# Schematic.net
KiCad netlist of a schematic drawn in EAGLE
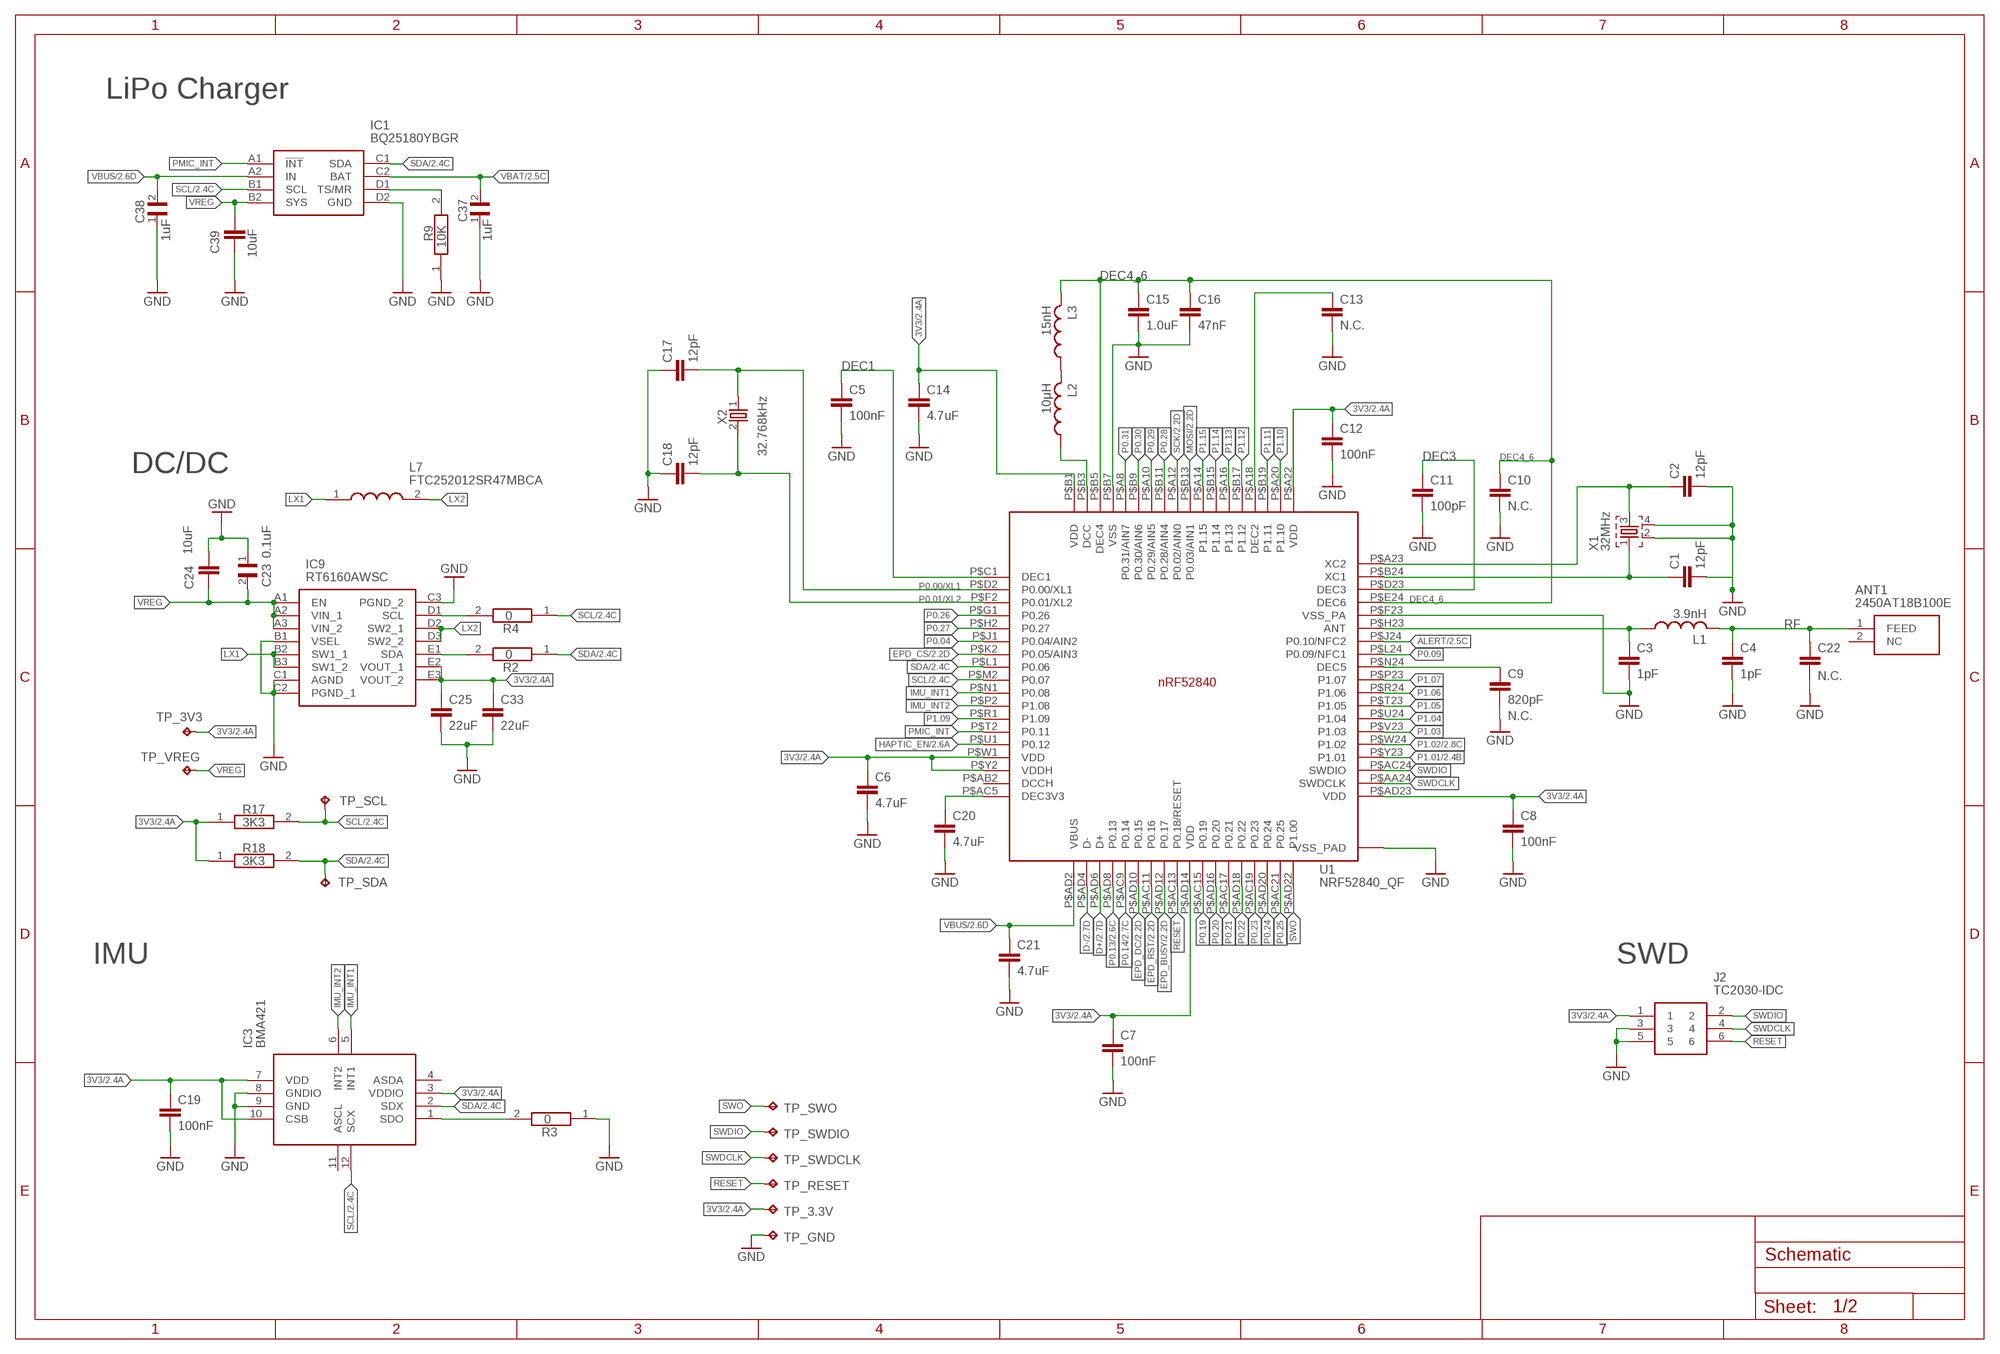
[diagram p0: schematic, sheet 1]
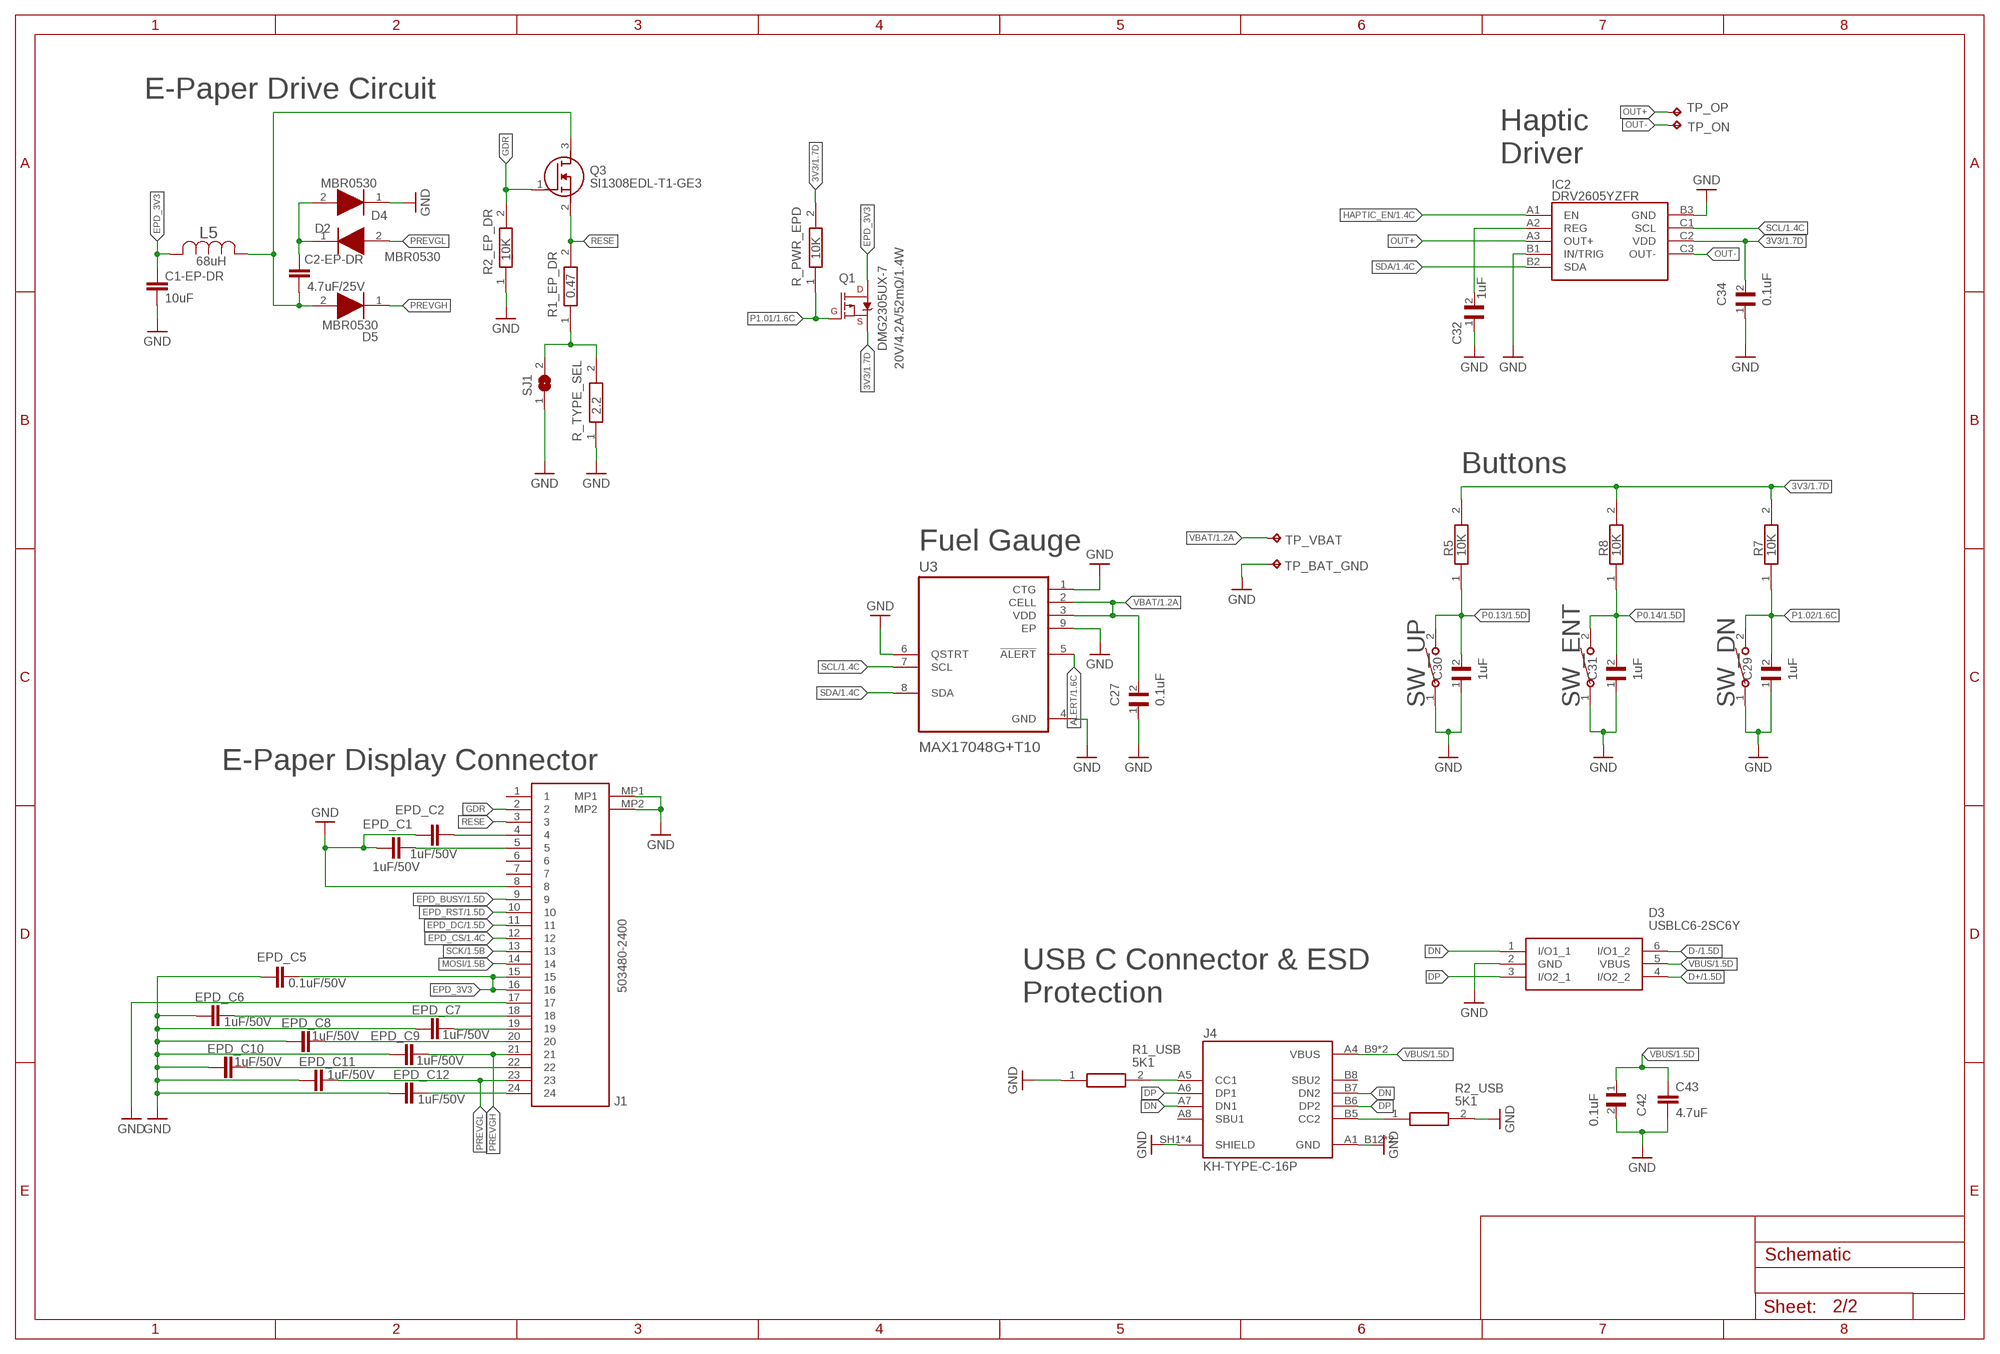
[diagram p1: schematic, sheet 2]

(export (version "E")
  (design (tool "Eeschema 10.0.6"))
  (components
    (comp (ref "ANT1")
      (value "2450AT18B100E")
      (footprint "eagle-import:2450AT18B100E_ANTC3216X140N")
      (fields (field (name "MOUSER_PART_NUMBER") "609-2450AT18B100E"))
      (libsource (lib "eagle-import") (part "2450AT18B100E_2450AT18B100E"))
    )
    (comp (ref "C1")
      (value "12pF")
      (footprint "eagle-import:NORDIC_NRF_3_RESC0201_L")
      (libsource (lib "eagle-import") (part "NORDIC_NRF_3_CAPACITOR_0201_L"))
    )
    (comp (ref "C2")
      (value "12pF")
      (footprint "eagle-import:NORDIC_NRF_3_RESC0201_L")
      (libsource (lib "eagle-import") (part "NORDIC_NRF_3_CAPACITOR_0201_L"))
    )
    (comp (ref "C3")
      (value "1pF")
      (footprint "eagle-import:NORDIC_NRF_3_RESC0201_L")
      (libsource (lib "eagle-import") (part "NORDIC_NRF_3_CAPACITOR_0201_L"))
    )
    (comp (ref "C4")
      (value "1pF")
      (footprint "eagle-import:NORDIC_NRF_3_RESC0201_L")
      (libsource (lib "eagle-import") (part "NORDIC_NRF_3_CAPACITOR_0201_L"))
    )
    (comp (ref "C5")
      (value "100nF")
      (footprint "eagle-import:NORDIC_NRF_3_RESC0201_L")
      (libsource (lib "eagle-import") (part "NORDIC_NRF_3_CAPACITOR_0201_L"))
    )
    (comp (ref "C6")
      (value "4.7uF")
      (footprint "eagle-import:NORDIC_NRF_3_RESC0402_L")
      (libsource (lib "eagle-import") (part "NORDIC_NRF_3_CAPACITOR_0402_L"))
    )
    (comp (ref "C7")
      (value "100nF")
      (footprint "eagle-import:NORDIC_NRF_3_RESC0201_L")
      (libsource (lib "eagle-import") (part "NORDIC_NRF_3_CAPACITOR_0201_L"))
    )
    (comp (ref "C8")
      (value "100nF")
      (footprint "eagle-import:NORDIC_NRF_3_RESC0201_L")
      (libsource (lib "eagle-import") (part "NORDIC_NRF_3_CAPACITOR_0201_L"))
    )
    (comp (ref "C9")
      (value "820pF")
      (footprint "eagle-import:NORDIC_NRF_3_RESC0201_L")
      (libsource (lib "eagle-import") (part "NORDIC_NRF_3_CAPACITOR_0201_L"))
    )
    (comp (ref "C10")
      (value "N.C.")
      (footprint "eagle-import:NORDIC_NRF_3_RESC0201_L")
      (libsource (lib "eagle-import") (part "NORDIC_NRF_3_CAPACITOR_0201_L"))
    )
    (comp (ref "C11")
      (value "100pF")
      (footprint "eagle-import:NORDIC_NRF_3_RESC0201_L")
      (libsource (lib "eagle-import") (part "NORDIC_NRF_3_CAPACITOR_0201_L"))
    )
    (comp (ref "C12")
      (value "100nF")
      (footprint "eagle-import:NORDIC_NRF_3_RESC0201_L")
      (libsource (lib "eagle-import") (part "NORDIC_NRF_3_CAPACITOR_0201_L"))
    )
    (comp (ref "C13")
      (value "N.C.")
      (footprint "eagle-import:NORDIC_NRF_3_RESC0201_L")
      (libsource (lib "eagle-import") (part "NORDIC_NRF_3_CAPACITOR_0201_L"))
    )
    (comp (ref "C14")
      (value "4.7uF")
      (footprint "eagle-import:NORDIC_NRF_3_RESC0402_L")
      (libsource (lib "eagle-import") (part "NORDIC_NRF_3_CAPACITOR_0402_L"))
    )
    (comp (ref "C15")
      (value "1.0uF")
      (footprint "eagle-import:NORDIC_NRF_3_RESC0402_L")
      (libsource (lib "eagle-import") (part "NORDIC_NRF_3_CAPACITOR_0402_L"))
    )
    (comp (ref "C16")
      (value "47nF")
      (footprint "eagle-import:NORDIC_NRF_3_RESC0201_L")
      (libsource (lib "eagle-import") (part "NORDIC_NRF_3_CAPACITOR_0201_L"))
    )
    (comp (ref "C17")
      (value "12pF")
      (footprint "eagle-import:NORDIC_NRF_3_RESC0201_L")
      (libsource (lib "eagle-import") (part "NORDIC_NRF_3_CAPACITOR_0201_L"))
    )
    (comp (ref "C18")
      (value "12pF")
      (footprint "eagle-import:NORDIC_NRF_3_RESC0201_L")
      (libsource (lib "eagle-import") (part "NORDIC_NRF_3_CAPACITOR_0201_L"))
    )
    (comp (ref "C19")
      (value "100nF")
      (footprint "eagle-import:NORDIC_NRF_3_RESC0201_L")
      (libsource (lib "eagle-import") (part "NORDIC_NRF_3_CAPACITOR_0201_L"))
    )
    (comp (ref "C20")
      (value "4.7uF")
      (footprint "eagle-import:NORDIC_NRF_3_RESC0402_L")
      (libsource (lib "eagle-import") (part "NORDIC_NRF_3_CAPACITOR_0402_L"))
    )
    (comp (ref "C21")
      (value "4.7uF")
      (footprint "eagle-import:NORDIC_NRF_3_RESC0402_L")
      (libsource (lib "eagle-import") (part "NORDIC_NRF_3_CAPACITOR_0402_L"))
    )
    (comp (ref "C22")
      (value "N.C.")
      (footprint "eagle-import:NORDIC_NRF_3_RESC0201_L")
      (libsource (lib "eagle-import") (part "NORDIC_NRF_3_CAPACITOR_0201_L"))
    )
    (comp (ref "C23")
      (value "0.1uF")
      (footprint "eagle-import:GRM011R60J152KE01L_1_0201")
      (libsource (lib "eagle-import") (part "GRM011R60J152KE01L_1_GRM011R60J152KE01L"))
    )
    (comp (ref "C24")
      (value "10uF")
      (footprint "eagle-import:NORDIC_NRF_3_RESC0402_L")
      (libsource (lib "eagle-import") (part "NORDIC_NRF_3_CAPACITOR_0402_L"))
    )
    (comp (ref "C25")
      (value "22uF")
      (footprint "eagle-import:NORDIC_NRF_3_RESC0402_L")
      (libsource (lib "eagle-import") (part "NORDIC_NRF_3_CAPACITOR_0402_L"))
    )
    (comp (ref "C33")
      (value "22uF")
      (footprint "eagle-import:NORDIC_NRF_3_RESC0402_L")
      (libsource (lib "eagle-import") (part "NORDIC_NRF_3_CAPACITOR_0402_L"))
    )
    (comp (ref "C37")
      (value "1uF")
      (footprint "eagle-import:GRM011R60J152KE01L_1_0201")
      (libsource (lib "eagle-import") (part "GRM011R60J152KE01L_1_GRM011R60J152KE01L"))
    )
    (comp (ref "C38")
      (value "1uF")
      (footprint "eagle-import:GRM011R60J152KE01L_1_0201")
      (libsource (lib "eagle-import") (part "GRM011R60J152KE01L_1_GRM011R60J152KE01L"))
    )
    (comp (ref "C39")
      (value "10uF")
      (footprint "eagle-import:NORDIC_NRF_3_RESC0402_L")
      (libsource (lib "eagle-import") (part "NORDIC_NRF_3_CAPACITOR_0402_L"))
    )
    (comp (ref "IC1")
      (value "BQ25180YBGR")
      (footprint "eagle-import:BQ25180YBGR_BGA8C40P2X4_100X155X50")
      (fields (field (name "MOUSER_PART_NUMBER") "595-BQ25180YBGR"))
      (libsource (lib "eagle-import") (part "BQ25180YBGR_BQ25180YBGR"))
    )
    (comp (ref "IC3")
      (value "BMA421")
      (footprint "eagle-import:BMA423_BMA423")
      (fields (field (name "ARROW_PART_NUMBER") "BMA423") (field (name "MOUSER_PART_NUMBER") "262-BMA423"))
      (libsource (lib "eagle-import") (part "BMA423_BMA423"))
    )
    (comp (ref "IC9")
      (value "RT6160AWSC")
      (footprint "eagle-import:RT6160AWSC_BGA15C40P3X5_140X230X60")
      (fields (field (name "MOUSER_PART_NUMBER") "835-RT6160AWSC"))
      (libsource (lib "eagle-import") (part "RT6160AWSC_RT6160AWSC"))
    )
    (comp (ref "J2")
      (value "TC2030-IDC")
      (footprint "eagle-import:TC2030-IDC_TC2030IDC")
      (libsource (lib "eagle-import") (part "TC2030-IDC_TC2030-IDC"))
    )
    (comp (ref "L1")
      (value "3.9nH")
      (footprint "eagle-import:NORDIC_NRF_2_RESC0402_L")
      (libsource (lib "eagle-import") (part "NORDIC_NRF_2_INDUCTOR_0402_L"))
    )
    (comp (ref "L2")
      (value "10μH")
      (footprint "eagle-import:NORDIC_NRF_2_RESC0402_L")
      (libsource (lib "eagle-import") (part "NORDIC_NRF_2_INDUCTOR_0402_L"))
    )
    (comp (ref "L3")
      (value "15nH")
      (footprint "eagle-import:NORDIC_NRF_2_RESC0402_L")
      (libsource (lib "eagle-import") (part "NORDIC_NRF_2_INDUCTOR_0402_L"))
    )
    (comp (ref "L7")
      (value "FTC252012SR47MBCA")
      (footprint "eagle-import:MLP2016SR47MT0S1_INDC2016X100N")
      (libsource (lib "eagle-import") (part "MLP2016SR47MT0S1_FTC252012SR47MBCA"))
    )
    (comp (ref "R2")
      (value "0")
      (footprint "eagle-import:ERA-1AEB3401C_0201")
      (libsource (lib "eagle-import") (part "ERA-1AEB3401C_CPF0201D7K68C1"))
    )
    (comp (ref "R3")
      (value "0")
      (footprint "eagle-import:ERA-1AEB3401C_0201")
      (libsource (lib "eagle-import") (part "ERA-1AEB3401C_CPF0201D7K68C1"))
    )
    (comp (ref "R4")
      (value "0")
      (footprint "eagle-import:ERA-1AEB3401C_0201")
      (libsource (lib "eagle-import") (part "ERA-1AEB3401C_CPF0201D7K68C1"))
    )
    (comp (ref "R9")
      (value "10K")
      (footprint "eagle-import:ERA-1AEB3401C_0201")
      (libsource (lib "eagle-import") (part "ERA-1AEB3401C_CPF0201D7K68C1"))
    )
    (comp (ref "R17")
      (value "3K3")
      (footprint "eagle-import:ERA-1AEB3401C_0201")
      (libsource (lib "eagle-import") (part "ERA-1AEB3401C_CPF0201D7K68C1"))
    )
    (comp (ref "R18")
      (value "3K3")
      (footprint "eagle-import:ERA-1AEB3401C_0201")
      (libsource (lib "eagle-import") (part "ERA-1AEB3401C_CPF0201D7K68C1"))
    )
    (comp (ref "TP_3.3V")
      (value "HECTOR_WATCH_1_TPTP20R")
      (footprint "eagle-import:HECTOR_WATCH_1_TP20R")
      (libsource (lib "eagle-import") (part "HECTOR_WATCH_1_TPTP20R"))
    )
    (comp (ref "TP_3V3")
      (value "HECTOR_WATCH_1_TPTP20R")
      (footprint "eagle-import:HECTOR_WATCH_1_TP20R")
      (libsource (lib "eagle-import") (part "HECTOR_WATCH_1_TPTP20R"))
    )
    (comp (ref "TP_GND")
      (value "HECTOR_WATCH_1_TPTP20R")
      (footprint "eagle-import:HECTOR_WATCH_1_TP20R")
      (libsource (lib "eagle-import") (part "HECTOR_WATCH_1_TPTP20R"))
    )
    (comp (ref "TP_RESET")
      (value "HECTOR_WATCH_1_TPTP20R")
      (footprint "eagle-import:HECTOR_WATCH_1_TP20R")
      (libsource (lib "eagle-import") (part "HECTOR_WATCH_1_TPTP20R"))
    )
    (comp (ref "TP_SCL")
      (value "HECTOR_WATCH_1_TPTP20R")
      (footprint "eagle-import:HECTOR_WATCH_1_TP20R")
      (libsource (lib "eagle-import") (part "HECTOR_WATCH_1_TPTP20R"))
    )
    (comp (ref "TP_SDA")
      (value "HECTOR_WATCH_1_TPTP20R")
      (footprint "eagle-import:HECTOR_WATCH_1_TP20R")
      (libsource (lib "eagle-import") (part "HECTOR_WATCH_1_TPTP20R"))
    )
    (comp (ref "TP_SWDCLK")
      (value "HECTOR_WATCH_1_TPTP20R")
      (footprint "eagle-import:HECTOR_WATCH_1_TP20R")
      (libsource (lib "eagle-import") (part "HECTOR_WATCH_1_TPTP20R"))
    )
    (comp (ref "TP_SWDIO")
      (value "HECTOR_WATCH_1_TPTP20R")
      (footprint "eagle-import:HECTOR_WATCH_1_TP20R")
      (libsource (lib "eagle-import") (part "HECTOR_WATCH_1_TPTP20R"))
    )
    (comp (ref "TP_SWO")
      (value "HECTOR_WATCH_1_TPTP20R")
      (footprint "eagle-import:HECTOR_WATCH_1_TP20R")
      (libsource (lib "eagle-import") (part "HECTOR_WATCH_1_TPTP20R"))
    )
    (comp (ref "TP_VREG")
      (value "HECTOR_WATCH_1_TPTP20R")
      (footprint "eagle-import:HECTOR_WATCH_1_TP20R")
      (libsource (lib "eagle-import") (part "HECTOR_WATCH_1_TPTP20R"))
    )
    (comp (ref "U1")
      (value "NRF52840_QF")
      (footprint "eagle-import:NORDIC_NRF_4_AQFN50P700X700X85_HS-74N")
      (libsource (lib "eagle-import") (part "NORDIC_NRF_4_NRF52840_QF"))
    )
    (comp (ref "X1")
      (value "32MHz")
      (footprint "eagle-import:NORDIC_NRF_BT-XTAL_2016_N")
      (libsource (lib "eagle-import") (part "NORDIC_NRF_XTAL_32MHZ"))
    )
    (comp (ref "X2")
      (value "32.768kHz")
      (footprint "eagle-import:NORDIC_NRF_1_XTAL_3215_N")
      (libsource (lib "eagle-import") (part "NORDIC_NRF_1_XTAL_32KHZ"))
    )
    (comp (ref "C1-EP-DR")
      (value "10uF")
      (footprint "eagle-import:NORDIC_NRF_3_RESC0402_L")
      (libsource (lib "eagle-import") (part "NORDIC_NRF_3_CAPACITOR_0402_L"))
    )
    (comp (ref "C2-EP-DR")
      (value "4.7uF/25V")
      (footprint "eagle-import:NORDIC_NRF_3_RESC0402_L")
      (libsource (lib "eagle-import") (part "NORDIC_NRF_3_CAPACITOR_0402_L"))
    )
    (comp (ref "C27")
      (value "0.1uF")
      (footprint "eagle-import:GRM011R60J152KE01L_1_0201")
      (libsource (lib "eagle-import") (part "GRM011R60J152KE01L_1_GRM011R60J152KE01L"))
    )
    (comp (ref "C29")
      (value "1uF")
      (footprint "eagle-import:GRM011R60J152KE01L_1_0201")
      (libsource (lib "eagle-import") (part "GRM011R60J152KE01L_1_GRM011R60J152KE01L"))
    )
    (comp (ref "C30")
      (value "1uF")
      (footprint "eagle-import:GRM011R60J152KE01L_1_0201")
      (libsource (lib "eagle-import") (part "GRM011R60J152KE01L_1_GRM011R60J152KE01L"))
    )
    (comp (ref "C31")
      (value "1uF")
      (footprint "eagle-import:GRM011R60J152KE01L_1_0201")
      (libsource (lib "eagle-import") (part "GRM011R60J152KE01L_1_GRM011R60J152KE01L"))
    )
    (comp (ref "C32")
      (value "1uF")
      (footprint "eagle-import:GRM011R60J152KE01L_1_0201")
      (libsource (lib "eagle-import") (part "GRM011R60J152KE01L_1_GRM011R60J152KE01L"))
    )
    (comp (ref "C34")
      (value "0.1uF")
      (footprint "eagle-import:GRM011R60J152KE01L_1_0201")
      (libsource (lib "eagle-import") (part "GRM011R60J152KE01L_1_GRM011R60J152KE01L"))
    )
    (comp (ref "C42")
      (value "0.1uF")
      (footprint "eagle-import:GRM011R60J152KE01L_1_0201")
      (libsource (lib "eagle-import") (part "GRM011R60J152KE01L_1_GRM011R60J152KE01L"))
    )
    (comp (ref "C43")
      (value "4.7uF")
      (footprint "eagle-import:NORDIC_NRF_3_RESC0402_L")
      (libsource (lib "eagle-import") (part "NORDIC_NRF_3_CAPACITOR_0402_L"))
    )
    (comp (ref "D2")
      (value "MBR0530")
      (footprint "eagle-import:ESP32_C6_LIBRARY_5_SOD3716X135N")
      (fields (field (name "MF") "ON Semiconductor"))
      (libsource (lib "eagle-import") (part "ESP32_C6_LIBRARY_5_MBR0530"))
    )
    (comp (ref "D3")
      (value "USBLC6-2SC6Y")
      (footprint "eagle-import:ESP32_C6_LIBRARY_3_SOT95P280X145-6N")
      (fields (field (name "MF") "STMicroelectronics"))
      (libsource (lib "eagle-import") (part "ESP32_C6_LIBRARY_3_USBLC6-2SC6Y"))
    )
    (comp (ref "D4")
      (value "MBR0530")
      (footprint "eagle-import:ESP32_C6_LIBRARY_5_SOD3716X135N")
      (fields (field (name "MF") "ON Semiconductor"))
      (libsource (lib "eagle-import") (part "ESP32_C6_LIBRARY_5_MBR0530"))
    )
    (comp (ref "D5")
      (value "MBR0530")
      (footprint "eagle-import:ESP32_C6_LIBRARY_5_SOD3716X135N")
      (fields (field (name "MF") "ON Semiconductor"))
      (libsource (lib "eagle-import") (part "ESP32_C6_LIBRARY_5_MBR0530"))
    )
    (comp (ref "EPD_C1")
      (value "1uF/50V")
      (footprint "eagle-import:NORDIC_NRF_3_RESC0402_L")
      (libsource (lib "eagle-import") (part "NORDIC_NRF_3_CAPACITOR_0402_L"))
    )
    (comp (ref "EPD_C2")
      (value "1uF/50V")
      (footprint "eagle-import:NORDIC_NRF_3_RESC0402_L")
      (libsource (lib "eagle-import") (part "NORDIC_NRF_3_CAPACITOR_0402_L"))
    )
    (comp (ref "EPD_C5")
      (value "0.1uF/50V")
      (footprint "eagle-import:NORDIC_NRF_3_RESC0201_L")
      (libsource (lib "eagle-import") (part "NORDIC_NRF_3_CAPACITOR_0201_L"))
    )
    (comp (ref "EPD_C6")
      (value "1uF/50V")
      (footprint "eagle-import:NORDIC_NRF_3_RESC0402_L")
      (libsource (lib "eagle-import") (part "NORDIC_NRF_3_CAPACITOR_0402_L"))
    )
    (comp (ref "EPD_C7")
      (value "1uF/50V")
      (footprint "eagle-import:NORDIC_NRF_3_RESC0402_L")
      (libsource (lib "eagle-import") (part "NORDIC_NRF_3_CAPACITOR_0402_L"))
    )
    (comp (ref "EPD_C8")
      (value "1uF/50V")
      (footprint "eagle-import:NORDIC_NRF_3_RESC0402_L")
      (libsource (lib "eagle-import") (part "NORDIC_NRF_3_CAPACITOR_0402_L"))
    )
    (comp (ref "EPD_C9")
      (value "1uF/50V")
      (footprint "eagle-import:NORDIC_NRF_3_RESC0402_L")
      (libsource (lib "eagle-import") (part "NORDIC_NRF_3_CAPACITOR_0402_L"))
    )
    (comp (ref "EPD_C10")
      (value "1uF/50V")
      (footprint "eagle-import:NORDIC_NRF_3_RESC0402_L")
      (libsource (lib "eagle-import") (part "NORDIC_NRF_3_CAPACITOR_0402_L"))
    )
    (comp (ref "EPD_C11")
      (value "1uF/50V")
      (footprint "eagle-import:NORDIC_NRF_3_RESC0402_L")
      (libsource (lib "eagle-import") (part "NORDIC_NRF_3_CAPACITOR_0402_L"))
    )
    (comp (ref "EPD_C12")
      (value "1uF/50V")
      (footprint "eagle-import:NORDIC_NRF_3_RESC0402_L")
      (libsource (lib "eagle-import") (part "NORDIC_NRF_3_CAPACITOR_0402_L"))
    )
    (comp (ref "IC2")
      (value "DRV2605YZFR")
      (footprint "eagle-import:DRV2605YZFR_BGA9C50P3X3_144X144X62")
      (libsource (lib "eagle-import") (part "DRV2605YZFR_DRV2605YZFR"))
    )
    (comp (ref "J1")
      (value "503480-2400")
      (footprint "eagle-import:503480-2400_5034802400")
      (fields (field (name "MOUSER_PART_NUMBER") "538-503480-2400"))
      (libsource (lib "eagle-import") (part "503480-2400_503480-2400"))
    )
    (comp (ref "J4")
      (value "KH-TYPE-C-16P")
      (footprint "eagle-import:KH-TYPE-C-16P_KINGHELM_KH-TYPE-C-16P")
      (fields (field (name "MF") "kinghelm"))
      (libsource (lib "eagle-import") (part "KH-TYPE-C-16P_KH-TYPE-C-16P"))
    )
    (comp (ref "L5")
      (value "68uH")
      (footprint "eagle-import:ESP32_C6_LIBRARY_2_IND_4828-WE-TPC_WRE")
      (fields
        (field (name "MANUFACTURER_PART_NUMBER") "744043680")
        (field (name "COPYRIGHT") "Copyright (C) 2024 Ultra Librarian. All rights reserved.")
      )
      (libsource (lib "eagle-import") (part "ESP32_C6_LIBRARY_2_744043680IND_4828-WE-TPC_WRE"))
    )
    (comp (ref "Q1")
      (value "20V/4.2A/52mΩ/1.4W")
      (footprint "eagle-import:ESP32_C6_LIBRARY_4_ESP32_C6_LIBRARY_4_ESP32_C6_LIBRARY_4_ESP32_C6_LIBRARY_4_ESP32_WROVER_SPARKFUN-DISCRETESEMI_SOT23-3")
      (libsource (lib "eagle-import") (part "ESP32_C6_LIBRARY_4_ESP32_WROVER_SPARKFUN-DISCRETESEMI_MOSFET_PCH-DMG2305UX-7"))
    )
    (comp (ref "Q3")
      (value "SI1308EDL-T1-GE3")
      (footprint "eagle-import:ESP32_C6_LIBRARY_6_SOT65P210X110-3N")
      (fields (field (name "MF") "Vishay Siliconix"))
      (libsource (lib "eagle-import") (part "ESP32_C6_LIBRARY_6_SI1308EDL-T1-GE3"))
    )
    (comp (ref "R1_EP_DR")
      (value "0.47")
      (footprint "eagle-import:ERA-1AEB3401C_0201")
      (libsource (lib "eagle-import") (part "ERA-1AEB3401C_CPF0201D7K68C1"))
    )
    (comp (ref "R1_USB")
      (value "5K1")
      (footprint "eagle-import:ERA-1AEB3401C_0201")
      (libsource (lib "eagle-import") (part "ERA-1AEB3401C_CPF0201D7K68C1"))
    )
    (comp (ref "R2_EP_DR")
      (value "10K")
      (footprint "eagle-import:ERA-1AEB3401C_0201")
      (libsource (lib "eagle-import") (part "ERA-1AEB3401C_CPF0201D7K68C1"))
    )
    (comp (ref "R2_USB")
      (value "5K1")
      (footprint "eagle-import:ERA-1AEB3401C_0201")
      (libsource (lib "eagle-import") (part "ERA-1AEB3401C_CPF0201D7K68C1"))
    )
    (comp (ref "R5")
      (value "10K")
      (footprint "eagle-import:ERA-1AEB3401C_0201")
      (libsource (lib "eagle-import") (part "ERA-1AEB3401C_CPF0201D7K68C1"))
    )
    (comp (ref "R7")
      (value "10K")
      (footprint "eagle-import:ERA-1AEB3401C_0201")
      (libsource (lib "eagle-import") (part "ERA-1AEB3401C_CPF0201D7K68C1"))
    )
    (comp (ref "R8")
      (value "10K")
      (footprint "eagle-import:ERA-1AEB3401C_0201")
      (libsource (lib "eagle-import") (part "ERA-1AEB3401C_CPF0201D7K68C1"))
    )
    (comp (ref "R_PWR_EPD")
      (value "10K")
      (footprint "eagle-import:ERA-1AEB3401C_0201")
      (libsource (lib "eagle-import") (part "ERA-1AEB3401C_CPF0201D7K68C1"))
    )
    (comp (ref "R_TYPE_SEL")
      (value "2.2")
      (footprint "eagle-import:ERA-1AEB3401C_0201")
      (libsource (lib "eagle-import") (part "ERA-1AEB3401C_CPF0201D7K68C1"))
    )
    (comp (ref "SJ1")
      (value "ESP32_C6_LIBRARY_7_JUMPER_SJ")
      (footprint "eagle-import:ESP32_C6_LIBRARY_7_JUMPER_SJ")
      (libsource (lib "eagle-import") (part "ESP32_C6_LIBRARY_7_JUMPER_SJ"))
    )
    (comp (ref "SW_DN")
      (value "2025-10-22_07-23-44_LIBRARY_EVP-AKE31ASW_EVP-AKE31A_PAN")
      (footprint "eagle-import:2025-10-22_07-23-44_LIBRARY_SW_EVP-AKE31A_PAN")
      (fields
        (field (name "MANUFACTURER_PART_NUMBER") "EVP-AKE31A")
        (field (name "COPYRIGHT") "Copyright (C) 2025 Ultra Librarian. All rights reserved.")
      )
      (libsource (lib "eagle-import") (part "2025-10-22_07-23-44_LIBRARY_EVP-AKE31ASW_EVP-AKE31A_PAN"))
    )
    (comp (ref "SW_ENT")
      (value "2025-10-22_07-23-44_LIBRARY_EVP-AKE31ASW_EVP-AKE31A_PAN")
      (footprint "eagle-import:2025-10-22_07-23-44_LIBRARY_SW_EVP-AKE31A_PAN")
      (fields
        (field (name "MANUFACTURER_PART_NUMBER") "EVP-AKE31A")
        (field (name "COPYRIGHT") "Copyright (C) 2025 Ultra Librarian. All rights reserved.")
      )
      (libsource (lib "eagle-import") (part "2025-10-22_07-23-44_LIBRARY_EVP-AKE31ASW_EVP-AKE31A_PAN"))
    )
    (comp (ref "SW_UP")
      (value "2025-10-22_07-23-44_LIBRARY_EVP-AKE31ASW_EVP-AKE31A_PAN")
      (footprint "eagle-import:2025-10-22_07-23-44_LIBRARY_SW_EVP-AKE31A_PAN")
      (fields
        (field (name "MANUFACTURER_PART_NUMBER") "EVP-AKE31A")
        (field (name "COPYRIGHT") "Copyright (C) 2025 Ultra Librarian. All rights reserved.")
      )
      (libsource (lib "eagle-import") (part "2025-10-22_07-23-44_LIBRARY_EVP-AKE31ASW_EVP-AKE31A_PAN"))
    )
    (comp (ref "TP_BAT_GND")
      (value "HECTOR_WATCH_1_TPTP20R")
      (footprint "eagle-import:HECTOR_WATCH_1_TP20R")
      (libsource (lib "eagle-import") (part "HECTOR_WATCH_1_TPTP20R"))
    )
    (comp (ref "TP_ON")
      (value "HECTOR_WATCH_1_TPTP20R")
      (footprint "eagle-import:HECTOR_WATCH_1_TP20R")
      (libsource (lib "eagle-import") (part "HECTOR_WATCH_1_TPTP20R"))
    )
    (comp (ref "TP_OP")
      (value "HECTOR_WATCH_1_TPTP20R")
      (footprint "eagle-import:HECTOR_WATCH_1_TP20R")
      (libsource (lib "eagle-import") (part "HECTOR_WATCH_1_TPTP20R"))
    )
    (comp (ref "TP_VBAT")
      (value "HECTOR_WATCH_1_TPTP20R")
      (footprint "eagle-import:HECTOR_WATCH_1_TP20R")
      (libsource (lib "eagle-import") (part "HECTOR_WATCH_1_TPTP20R"))
    )
    (comp (ref "U3")
      (value "MAX17048G+T10")
      (footprint "eagle-import:ESP32_C6_LIBRARY_SON50P200X200X80-9N")
      (fields (field (name "MF") "Analog Devices"))
      (libsource (lib "eagle-import") (part "ESP32_C6_LIBRARY_MAX17048G+T10"))
    )
  )
  (nets
    (net (code "1") (name "3V3{slash}1.7D") (class "Default")
      (node (ref "C34") (pin "2") (pinfunction "2_2") (pintype "passive"))
      (node (ref "IC2") (pin "C2") (pinfunction "VDD_C2") (pintype "bidirectional"))
      (node (ref "Q1") (pin "2") (pinfunction "S_2") (pintype "bidirectional"))
      (node (ref "R5") (pin "2") (pinfunction "2_2") (pintype "bidirectional"))
      (node (ref "R7") (pin "2") (pinfunction "2_2") (pintype "bidirectional"))
      (node (ref "R8") (pin "2") (pinfunction "2_2") (pintype "bidirectional"))
      (node (ref "R_PWR_EPD") (pin "2") (pinfunction "2_2") (pintype "bidirectional"))
    )
    (net (code "2") (name "3V3{slash}2.4A") (class "Default")
      (node (ref "C12") (pin "1") (pinfunction "1_1") (pintype "passive"))
      (node (ref "C14") (pin "1") (pinfunction "1_1") (pintype "passive"))
      (node (ref "C19") (pin "1") (pinfunction "1_1") (pintype "passive"))
      (node (ref "C25") (pin "1") (pinfunction "1_1") (pintype "passive"))
      (node (ref "C33") (pin "1") (pinfunction "1_1") (pintype "passive"))
      (node (ref "C6") (pin "1") (pinfunction "1_1") (pintype "passive"))
      (node (ref "C7") (pin "1") (pinfunction "1_1") (pintype "passive"))
      (node (ref "C8") (pin "1") (pinfunction "1_1") (pintype "passive"))
      (node (ref "IC3") (pin "10") (pinfunction "CSB_10") (pintype "bidirectional"))
      (node (ref "IC3") (pin "3") (pinfunction "VDDIO_3") (pintype "bidirectional"))
      (node (ref "IC3") (pin "7") (pinfunction "VDD_7") (pintype "bidirectional"))
      (node (ref "IC9") (pin "E2") (pinfunction "VOUT_1_E2") (pintype "bidirectional"))
      (node (ref "IC9") (pin "E3") (pinfunction "VOUT_2_E3") (pintype "bidirectional"))
      (node (ref "J2") (pin "1") (pinfunction "1_1") (pintype "bidirectional"))
      (node (ref "R17") (pin "1") (pinfunction "1_1") (pintype "bidirectional"))
      (node (ref "R18") (pin "1") (pinfunction "1_1") (pintype "bidirectional"))
      (node (ref "TP_3.3V") (pin "TP") (pinfunction "TP_TP") (pintype "input"))
      (node (ref "TP_3V3") (pin "TP") (pinfunction "TP_TP") (pintype "input"))
      (node (ref "U1") (pin "P$A22") (pinfunction "VDD_P$A22") (pintype "power_in"))
      (node (ref "U1") (pin "P$AD14") (pinfunction "VDD_P$AD14") (pintype "power_in"))
      (node (ref "U1") (pin "P$AD23") (pinfunction "VDD_P$AD23") (pintype "power_in"))
      (node (ref "U1") (pin "P$B1") (pinfunction "VDD_P$B1") (pintype "power_in"))
      (node (ref "U1") (pin "P$W1") (pinfunction "VDD_P$W1") (pintype "power_in"))
      (node (ref "U1") (pin "P$Y2") (pinfunction "VDDH_P$Y2") (pintype "power_in"))
    )
    (net (code "3") (name "ALERT{slash}1.6C") (class "Default")
      (node (ref "U3") (pin "5") (pinfunction "~{ALERT}_5") (pintype "output"))
    )
    (net (code "4") (name "ALERT{slash}2.5C") (class "Default")
      (node (ref "U1") (pin "P$J24") (pinfunction "P0.10/NFC2_P$J24") (pintype "bidirectional"))
    )
    (net (code "5") (name "D+{slash}1.5D") (class "Default")
      (node (ref "D3") (pin "4") (pinfunction "I/O2_2_4") (pintype "bidirectional"))
    )
    (net (code "6") (name "D+{slash}2.7D") (class "Default")
      (node (ref "U1") (pin "P$AD6") (pinfunction "D+_P$AD6") (pintype "bidirectional"))
    )
    (net (code "7") (name "D-{slash}1.5D") (class "Default")
      (node (ref "D3") (pin "6") (pinfunction "I/O1_2_6") (pintype "bidirectional"))
    )
    (net (code "8") (name "D-{slash}2.7D") (class "Default")
      (node (ref "U1") (pin "P$AD4") (pinfunction "D-_P$AD4") (pintype "bidirectional"))
    )
    (net (code "9") (name "DEC1") (class "Default")
      (node (ref "C5") (pin "1") (pinfunction "1_1") (pintype "passive"))
      (node (ref "U1") (pin "P$C1") (pinfunction "DEC1_P$C1") (pintype "power_in"))
    )
    (net (code "10") (name "DEC3") (class "Default")
      (node (ref "C11") (pin "1") (pinfunction "1_1") (pintype "passive"))
      (node (ref "U1") (pin "P$D23") (pinfunction "DEC3_P$D23") (pintype "bidirectional"))
    )
    (net (code "11") (name "DEC4_6") (class "Default")
      (node (ref "C10") (pin "1") (pinfunction "1_1") (pintype "passive"))
      (node (ref "C15") (pin "1") (pinfunction "1_1") (pintype "passive"))
      (node (ref "C16") (pin "1") (pinfunction "1_1") (pintype "passive"))
      (node (ref "L3") (pin "2") (pinfunction "2_2") (pintype "passive"))
      (node (ref "U1") (pin "P$B5") (pinfunction "DEC4_P$B5") (pintype "power_in"))
      (node (ref "U1") (pin "P$E24") (pinfunction "DEC6_P$E24") (pintype "bidirectional"))
    )
    (net (code "12") (name "DN") (class "Default")
      (node (ref "D3") (pin "1") (pinfunction "I/O1_1_1") (pintype "bidirectional"))
      (node (ref "J4") (pin "A7") (pinfunction "DN1_A7") (pintype "bidirectional"))
      (node (ref "J4") (pin "B7") (pinfunction "DN2_B7") (pintype "bidirectional"))
    )
    (net (code "13") (name "DP") (class "Default")
      (node (ref "D3") (pin "3") (pinfunction "I/O2_1_3") (pintype "bidirectional"))
      (node (ref "J4") (pin "A6") (pinfunction "DP1_A6") (pintype "bidirectional"))
      (node (ref "J4") (pin "B6") (pinfunction "DP2_B6") (pintype "bidirectional"))
    )
    (net (code "14") (name "EPD_3V3") (class "Default")
      (node (ref "C1-EP-DR") (pin "2") (pinfunction "2_2") (pintype "passive"))
      (node (ref "EPD_C5") (pin "2") (pinfunction "2_2") (pintype "passive"))
      (node (ref "J1") (pin "15") (pinfunction "15_15") (pintype "bidirectional"))
      (node (ref "J1") (pin "16") (pinfunction "16_16") (pintype "bidirectional"))
      (node (ref "L5") (pin "2") (pinfunction "2_2") (pintype "passive"))
      (node (ref "Q1") (pin "3") (pinfunction "D_3") (pintype "bidirectional"))
    )
    (net (code "15") (name "EPD_BUSY{slash}1.5D") (class "Default")
      (node (ref "J1") (pin "9") (pinfunction "9_9") (pintype "bidirectional"))
    )
    (net (code "16") (name "EPD_BUSY{slash}2.2D") (class "Default")
      (node (ref "U1") (pin "P$AD12") (pinfunction "P0.17_P$AD12") (pintype "bidirectional"))
    )
    (net (code "17") (name "EPD_CS{slash}1.4C") (class "Default")
      (node (ref "J1") (pin "12") (pinfunction "12_12") (pintype "bidirectional"))
    )
    (net (code "18") (name "EPD_CS{slash}2.2D") (class "Default")
      (node (ref "U1") (pin "P$K2") (pinfunction "P0.05/AIN3_P$K2") (pintype "bidirectional"))
    )
    (net (code "19") (name "EPD_DC{slash}1.5D") (class "Default")
      (node (ref "J1") (pin "11") (pinfunction "11_11") (pintype "bidirectional"))
    )
    (net (code "20") (name "EPD_DC{slash}2.2D") (class "Default")
      (node (ref "U1") (pin "P$AD10") (pinfunction "P0.15_P$AD10") (pintype "bidirectional"))
    )
    (net (code "21") (name "EPD_RST{slash}1.5D") (class "Default")
      (node (ref "J1") (pin "10") (pinfunction "10_10") (pintype "bidirectional"))
    )
    (net (code "22") (name "EPD_RST{slash}2.2D") (class "Default")
      (node (ref "U1") (pin "P$AC11") (pinfunction "P0.16_P$AC11") (pintype "bidirectional"))
    )
    (net (code "23") (name "GDR") (class "Default")
      (node (ref "J1") (pin "2") (pinfunction "2_2") (pintype "bidirectional"))
      (node (ref "Q3") (pin "1") (pinfunction "G_1") (pintype "bidirectional"))
      (node (ref "R2_EP_DR") (pin "2") (pinfunction "2_2") (pintype "bidirectional"))
    )
    (net (code "24") (name "GND") (class "Default")
      (node (ref "C1") (pin "2") (pinfunction "2_2") (pintype "passive"))
      (node (ref "C1-EP-DR") (pin "1") (pinfunction "1_1") (pintype "passive"))
      (node (ref "C10") (pin "2") (pinfunction "2_2") (pintype "passive"))
      (node (ref "C11") (pin "2") (pinfunction "2_2") (pintype "passive"))
      (node (ref "C12") (pin "2") (pinfunction "2_2") (pintype "passive"))
      (node (ref "C13") (pin "2") (pinfunction "2_2") (pintype "passive"))
      (node (ref "C14") (pin "2") (pinfunction "2_2") (pintype "passive"))
      (node (ref "C15") (pin "2") (pinfunction "2_2") (pintype "passive"))
      (node (ref "C16") (pin "2") (pinfunction "2_2") (pintype "passive"))
      (node (ref "C17") (pin "1") (pinfunction "1_1") (pintype "passive"))
      (node (ref "C18") (pin "1") (pinfunction "1_1") (pintype "passive"))
      (node (ref "C19") (pin "2") (pinfunction "2_2") (pintype "passive"))
      (node (ref "C2") (pin "2") (pinfunction "2_2") (pintype "passive"))
      (node (ref "C20") (pin "2") (pinfunction "2_2") (pintype "passive"))
      (node (ref "C21") (pin "2") (pinfunction "2_2") (pintype "passive"))
      (node (ref "C22") (pin "2") (pinfunction "2_2") (pintype "passive"))
      (node (ref "C23") (pin "1") (pinfunction "1_1") (pintype "passive"))
      (node (ref "C24") (pin "1") (pinfunction "1_1") (pintype "passive"))
      (node (ref "C25") (pin "2") (pinfunction "2_2") (pintype "passive"))
      (node (ref "C27") (pin "1") (pinfunction "1_1") (pintype "passive"))
      (node (ref "C29") (pin "1") (pinfunction "1_1") (pintype "passive"))
      (node (ref "C3") (pin "2") (pinfunction "2_2") (pintype "passive"))
      (node (ref "C30") (pin "1") (pinfunction "1_1") (pintype "passive"))
      (node (ref "C31") (pin "1") (pinfunction "1_1") (pintype "passive"))
      (node (ref "C32") (pin "1") (pinfunction "1_1") (pintype "passive"))
      (node (ref "C33") (pin "2") (pinfunction "2_2") (pintype "passive"))
      (node (ref "C34") (pin "1") (pinfunction "1_1") (pintype "passive"))
      (node (ref "C37") (pin "1") (pinfunction "1_1") (pintype "passive"))
      (node (ref "C38") (pin "1") (pinfunction "1_1") (pintype "passive"))
      (node (ref "C39") (pin "2") (pinfunction "2_2") (pintype "passive"))
      (node (ref "C4") (pin "2") (pinfunction "2_2") (pintype "passive"))
      (node (ref "C42") (pin "2") (pinfunction "2_2") (pintype "passive"))
      (node (ref "C43") (pin "1") (pinfunction "1_1") (pintype "passive"))
      (node (ref "C5") (pin "2") (pinfunction "2_2") (pintype "passive"))
      (node (ref "C6") (pin "2") (pinfunction "2_2") (pintype "passive"))
      (node (ref "C7") (pin "2") (pinfunction "2_2") (pintype "passive"))
      (node (ref "C8") (pin "2") (pinfunction "2_2") (pintype "passive"))
      (node (ref "C9") (pin "2") (pinfunction "2_2") (pintype "passive"))
      (node (ref "D3") (pin "2") (pinfunction "GND_2") (pintype "bidirectional"))
      (node (ref "D4") (pin "1") (pinfunction "K_1") (pintype "bidirectional"))
      (node (ref "EPD_C1") (pin "1") (pinfunction "1_1") (pintype "passive"))
      (node (ref "EPD_C10") (pin "1") (pinfunction "1_1") (pintype "passive"))
      (node (ref "EPD_C11") (pin "1") (pinfunction "1_1") (pintype "passive"))
      (node (ref "EPD_C12") (pin "1") (pinfunction "1_1") (pintype "passive"))
      (node (ref "EPD_C2") (pin "1") (pinfunction "1_1") (pintype "passive"))
      (node (ref "EPD_C5") (pin "1") (pinfunction "1_1") (pintype "passive"))
      (node (ref "EPD_C6") (pin "1") (pinfunction "1_1") (pintype "passive"))
      (node (ref "EPD_C7") (pin "1") (pinfunction "1_1") (pintype "passive"))
      (node (ref "EPD_C8") (pin "1") (pinfunction "1_1") (pintype "passive"))
      (node (ref "EPD_C9") (pin "1") (pinfunction "1_1") (pintype "passive"))
      (node (ref "IC1") (pin "D2") (pinfunction "GND_D2") (pintype "bidirectional"))
      (node (ref "IC2") (pin "B1") (pinfunction "IN/TRIG_B1") (pintype "bidirectional"))
      (node (ref "IC2") (pin "B3") (pinfunction "GND_B3") (pintype "bidirectional"))
      (node (ref "IC3") (pin "8") (pinfunction "GNDIO_8") (pintype "bidirectional"))
      (node (ref "IC3") (pin "9") (pinfunction "GND_9") (pintype "bidirectional"))
      (node (ref "IC9") (pin "B1") (pinfunction "VSEL_B1") (pintype "bidirectional"))
      (node (ref "IC9") (pin "C1") (pinfunction "AGND_C1") (pintype "bidirectional"))
      (node (ref "IC9") (pin "C2") (pinfunction "PGND_1_C2") (pintype "bidirectional"))
      (node (ref "IC9") (pin "C3") (pinfunction "PGND_2_C3") (pintype "bidirectional"))
      (node (ref "J1") (pin "17") (pinfunction "17_17") (pintype "bidirectional"))
      (node (ref "J1") (pin "8") (pinfunction "8_8") (pintype "bidirectional"))
      (node (ref "J1") (pin "MP1") (pinfunction "MP1_MP1") (pintype "bidirectional"))
      (node (ref "J1") (pin "MP2") (pinfunction "MP2_MP2") (pintype "bidirectional"))
      (node (ref "J2") (pin "3") (pinfunction "3_3") (pintype "bidirectional"))
      (node (ref "J2") (pin "5") (pinfunction "5_5") (pintype "bidirectional"))
      (node (ref "J4") (pin "A12_B1") (pinfunction "GND_A12_B1") (pintype "power_in"))
      (node (ref "J4") (pin "A1_B12") (pinfunction "GND_A1_B12") (pintype "power_in"))
      (node (ref "J4") (pin "SH1") (pinfunction "SHIELD_SH1") (pintype "passive"))
      (node (ref "J4") (pin "SH2") (pinfunction "SHIELD_SH2") (pintype "passive"))
      (node (ref "J4") (pin "SH3") (pinfunction "SHIELD_SH3") (pintype "passive"))
      (node (ref "J4") (pin "SH4") (pinfunction "SHIELD_SH4") (pintype "passive"))
      (node (ref "R1_USB") (pin "1") (pinfunction "1_1") (pintype "bidirectional"))
      (node (ref "R2_EP_DR") (pin "1") (pinfunction "1_1") (pintype "bidirectional"))
      (node (ref "R2_USB") (pin "2") (pinfunction "2_2") (pintype "bidirectional"))
      (node (ref "R3") (pin "1") (pinfunction "1_1") (pintype "bidirectional"))
      (node (ref "R9") (pin "1") (pinfunction "1_1") (pintype "bidirectional"))
      (node (ref "R_TYPE_SEL") (pin "1") (pinfunction "1_1") (pintype "bidirectional"))
      (node (ref "SJ1") (pin "1") (pinfunction "1_1") (pintype "passive"))
      (node (ref "SW_DN") (pin "1") (pinfunction "1_1") (pintype "passive"))
      (node (ref "SW_ENT") (pin "1") (pinfunction "1_1") (pintype "passive"))
      (node (ref "SW_UP") (pin "1") (pinfunction "1_1") (pintype "passive"))
      (node (ref "TP_BAT_GND") (pin "TP") (pinfunction "TP_TP") (pintype "input"))
      (node (ref "TP_GND") (pin "TP") (pinfunction "TP_TP") (pintype "input"))
      (node (ref "U1") (pin "P$74") (pinfunction "VSS_PAD_P$74") (pintype "bidirectional"))
      (node (ref "U1") (pin "P$75") (pinfunction "VSS_PAD_P$75") (pintype "bidirectional"))
      (node (ref "U1") (pin "P$76") (pinfunction "VSS_PAD_P$76") (pintype "bidirectional"))
      (node (ref "U1") (pin "P$77") (pinfunction "VSS_PAD_P$77") (pintype "bidirectional"))
      (node (ref "U1") (pin "P$78") (pinfunction "VSS_PAD_P$78") (pintype "bidirectional"))
      (node (ref "U1") (pin "P$79") (pinfunction "VSS_PAD_P$79") (pintype "bidirectional"))
      (node (ref "U1") (pin "P$80") (pinfunction "VSS_PAD_P$80") (pintype "bidirectional"))
      (node (ref "U1") (pin "P$81") (pinfunction "VSS_PAD_P$81") (pintype "bidirectional"))
      (node (ref "U1") (pin "P$82") (pinfunction "VSS_PAD_P$82") (pintype "bidirectional"))
      (node (ref "U1") (pin "P$83") (pinfunction "VSS_PAD_P$83") (pintype "bidirectional"))
      (node (ref "U1") (pin "P$84") (pinfunction "VSS_PAD_P$84") (pintype "bidirectional"))
      (node (ref "U1") (pin "P$85") (pinfunction "VSS_PAD_P$85") (pintype "bidirectional"))
      (node (ref "U1") (pin "P$86") (pinfunction "VSS_PAD_P$86") (pintype "bidirectional"))
      (node (ref "U1") (pin "P$87") (pinfunction "VSS_PAD_P$87") (pintype "bidirectional"))
      (node (ref "U1") (pin "P$88") (pinfunction "VSS_PAD_P$88") (pintype "bidirectional"))
      (node (ref "U1") (pin "P$89") (pinfunction "VSS_PAD_P$89") (pintype "bidirectional"))
      (node (ref "U1") (pin "P$90") (pinfunction "VSS_PAD_P$90") (pintype "bidirectional"))
      (node (ref "U1") (pin "P$B7") (pinfunction "VSS_P$B7") (pintype "power_in"))
      (node (ref "U1") (pin "P$F23") (pinfunction "VSS_PA_P$F23") (pintype "bidirectional"))
      (node (ref "U3") (pin "1") (pinfunction "CTG_1") (pintype "power_in"))
      (node (ref "U3") (pin "4") (pinfunction "GND_4") (pintype "power_in"))
      (node (ref "U3") (pin "6") (pinfunction "QSTRT_6") (pintype "input"))
      (node (ref "U3") (pin "9") (pinfunction "EP_9") (pintype "power_in"))
      (node (ref "X1") (pin "2") (pinfunction "2_2") (pintype "passive"))
      (node (ref "X1") (pin "4") (pinfunction "4_4") (pintype "passive"))
    )
    (net (code "25") (name "HAPTIC_EN{slash}1.4C") (class "Default")
      (node (ref "IC2") (pin "A1") (pinfunction "EN_A1") (pintype "bidirectional"))
    )
    (net (code "26") (name "HAPTIC_EN{slash}2.6A") (class "Default")
      (node (ref "U1") (pin "P$U1") (pinfunction "P0.12_P$U1") (pintype "bidirectional"))
    )
    (net (code "27") (name "IMU_INT1") (class "Default")
      (node (ref "IC3") (pin "5") (pinfunction "INT1_5") (pintype "bidirectional"))
      (node (ref "U1") (pin "P$N1") (pinfunction "P0.08_P$N1") (pintype "bidirectional"))
    )
    (net (code "28") (name "IMU_INT2") (class "Default")
      (node (ref "IC3") (pin "6") (pinfunction "INT2_6") (pintype "bidirectional"))
      (node (ref "U1") (pin "P$P2") (pinfunction "P1.08_P$P2") (pintype "bidirectional"))
    )
    (net (code "29") (name "LX1") (class "Default")
      (node (ref "IC9") (pin "B2") (pinfunction "SW1_1_B2") (pintype "bidirectional"))
      (node (ref "IC9") (pin "B3") (pinfunction "SW1_2_B3") (pintype "bidirectional"))
      (node (ref "L7") (pin "1") (pinfunction "1_1") (pintype "bidirectional"))
    )
    (net (code "30") (name "LX2") (class "Default")
      (node (ref "IC9") (pin "D2") (pinfunction "SW2_1_D2") (pintype "bidirectional"))
      (node (ref "IC9") (pin "D3") (pinfunction "SW2_2_D3") (pintype "bidirectional"))
      (node (ref "L7") (pin "2") (pinfunction "2_2") (pintype "bidirectional"))
    )
    (net (code "31") (name "MOSI{slash}1.5B") (class "Default")
      (node (ref "J1") (pin "14") (pinfunction "14_14") (pintype "bidirectional"))
    )
    (net (code "32") (name "MOSI{slash}2.2D") (class "Default")
      (node (ref "U1") (pin "P$B13") (pinfunction "P0.03/AIN1_P$B13") (pintype "bidirectional"))
    )
    (net (code "33") (name "Net-(D2-K)") (class "Default")
      (node (ref "C2-EP-DR") (pin "2") (pinfunction "2_2") (pintype "passive"))
      (node (ref "D2") (pin "1") (pinfunction "K_1") (pintype "bidirectional"))
      (node (ref "D4") (pin "2") (pinfunction "A_2") (pintype "bidirectional"))
    )
    (net (code "34") (name "Net-(D5-A)") (class "Default")
      (node (ref "C2-EP-DR") (pin "1") (pinfunction "1_1") (pintype "passive"))
      (node (ref "D5") (pin "2") (pinfunction "A_2") (pintype "bidirectional"))
      (node (ref "L5") (pin "1") (pinfunction "1_1") (pintype "passive"))
      (node (ref "Q3") (pin "3") (pinfunction "D_3") (pintype "bidirectional"))
    )
    (net (code "35") (name "Net-(EPD_C1-Pad2)") (class "Default")
      (node (ref "EPD_C1") (pin "2") (pinfunction "2_2") (pintype "passive"))
      (node (ref "J1") (pin "5") (pinfunction "5_5") (pintype "bidirectional"))
    )
    (net (code "36") (name "Net-(EPD_C2-Pad2)") (class "Default")
      (node (ref "EPD_C2") (pin "2") (pinfunction "2_2") (pintype "passive"))
      (node (ref "J1") (pin "4") (pinfunction "4_4") (pintype "bidirectional"))
    )
    (net (code "37") (name "Net-(EPD_C6-Pad2)") (class "Default")
      (node (ref "EPD_C6") (pin "2") (pinfunction "2_2") (pintype "passive"))
      (node (ref "J1") (pin "18") (pinfunction "18_18") (pintype "bidirectional"))
    )
    (net (code "38") (name "Net-(EPD_C7-Pad2)") (class "Default")
      (node (ref "EPD_C7") (pin "2") (pinfunction "2_2") (pintype "passive"))
      (node (ref "J1") (pin "19") (pinfunction "19_19") (pintype "bidirectional"))
    )
    (net (code "39") (name "Net-(EPD_C8-Pad2)") (class "Default")
      (node (ref "EPD_C8") (pin "2") (pinfunction "2_2") (pintype "passive"))
      (node (ref "J1") (pin "20") (pinfunction "20_20") (pintype "bidirectional"))
    )
    (net (code "40") (name "Net-(EPD_C10-Pad2)") (class "Default")
      (node (ref "EPD_C10") (pin "2") (pinfunction "2_2") (pintype "passive"))
      (node (ref "J1") (pin "22") (pinfunction "22_22") (pintype "bidirectional"))
    )
    (net (code "41") (name "Net-(EPD_C12-Pad2)") (class "Default")
      (node (ref "EPD_C12") (pin "2") (pinfunction "2_2") (pintype "passive"))
      (node (ref "J1") (pin "24") (pinfunction "24_24") (pintype "bidirectional"))
    )
    (net (code "42") (name "Net-(IC1-TS{slash}MR)") (class "Default")
      (node (ref "IC1") (pin "D1") (pinfunction "TS/MR_D1") (pintype "bidirectional"))
      (node (ref "R9") (pin "2") (pinfunction "2_2") (pintype "bidirectional"))
    )
    (net (code "43") (name "Net-(IC2-REG)") (class "Default")
      (node (ref "C32") (pin "2") (pinfunction "2_2") (pintype "passive"))
      (node (ref "IC2") (pin "A2") (pinfunction "REG_A2") (pintype "bidirectional"))
    )
    (net (code "44") (name "Net-(IC3-SDO)") (class "Default")
      (node (ref "IC3") (pin "1") (pinfunction "SDO_1") (pintype "bidirectional"))
      (node (ref "R3") (pin "2") (pinfunction "2_2") (pintype "bidirectional"))
    )
    (net (code "45") (name "Net-(IC9-SCL)") (class "Default")
      (node (ref "IC9") (pin "D1") (pinfunction "SCL_D1") (pintype "bidirectional"))
      (node (ref "R4") (pin "2") (pinfunction "2_2") (pintype "bidirectional"))
    )
    (net (code "46") (name "Net-(IC9-SDA)") (class "Default")
      (node (ref "IC9") (pin "E1") (pinfunction "SDA_E1") (pintype "bidirectional"))
      (node (ref "R2") (pin "2") (pinfunction "2_2") (pintype "bidirectional"))
    )
    (net (code "47") (name "Net-(J4-CC1)") (class "Default")
      (node (ref "J4") (pin "A5") (pinfunction "CC1_A5") (pintype "bidirectional"))
      (node (ref "R1_USB") (pin "2") (pinfunction "2_2") (pintype "bidirectional"))
    )
    (net (code "48") (name "Net-(J4-CC2)") (class "Default")
      (node (ref "J4") (pin "B5") (pinfunction "CC2_B5") (pintype "bidirectional"))
      (node (ref "R2_USB") (pin "1") (pinfunction "1_1") (pintype "bidirectional"))
    )
    (net (code "49") (name "Net-(L2-Pad2)") (class "Default")
      (node (ref "L2") (pin "2") (pinfunction "2_2") (pintype "passive"))
      (node (ref "L3") (pin "1") (pinfunction "1_1") (pintype "passive"))
    )
    (net (code "50") (name "Net-(R1_EP_DR-Pad1)") (class "Default")
      (node (ref "R1_EP_DR") (pin "1") (pinfunction "1_1") (pintype "bidirectional"))
      (node (ref "R_TYPE_SEL") (pin "2") (pinfunction "2_2") (pintype "bidirectional"))
      (node (ref "SJ1") (pin "2") (pinfunction "2_2") (pintype "passive"))
    )
    (net (code "51") (name "Net-(U1-ANT)") (class "Default")
      (node (ref "C3") (pin "1") (pinfunction "1_1") (pintype "passive"))
      (node (ref "L1") (pin "1") (pinfunction "1_1") (pintype "passive"))
      (node (ref "U1") (pin "P$H23") (pinfunction "ANT_P$H23") (pintype "bidirectional"))
    )
    (net (code "52") (name "Net-(U1-DCC)") (class "Default")
      (node (ref "L2") (pin "1") (pinfunction "1_1") (pintype "passive"))
      (node (ref "U1") (pin "P$B3") (pinfunction "DCC_P$B3") (pintype "output"))
    )
    (net (code "53") (name "Net-(U1-DEC2)") (class "Default")
      (node (ref "C13") (pin "1") (pinfunction "1_1") (pintype "passive"))
      (node (ref "U1") (pin "P$A18") (pinfunction "DEC2_P$A18") (pintype "bidirectional"))
    )
    (net (code "54") (name "Net-(U1-DEC3V3)") (class "Default")
      (node (ref "C20") (pin "1") (pinfunction "1_1") (pintype "passive"))
      (node (ref "U1") (pin "P$AC5") (pinfunction "DEC3V3_P$AC5") (pintype "bidirectional"))
    )
    (net (code "55") (name "Net-(U1-DEC5)") (class "Default")
      (node (ref "C9") (pin "1") (pinfunction "1_1") (pintype "passive"))
      (node (ref "U1") (pin "P$N24") (pinfunction "DEC5_P$N24") (pintype "bidirectional"))
    )
    (net (code "56") (name "Net-(U1-XC1)") (class "Default")
      (node (ref "C1") (pin "1") (pinfunction "1_1") (pintype "passive"))
      (node (ref "U1") (pin "P$B24") (pinfunction "XC1_P$B24") (pintype "input"))
      (node (ref "X1") (pin "1") (pinfunction "1_1") (pintype "passive"))
    )
    (net (code "57") (name "Net-(U1-XC2)") (class "Default")
      (node (ref "C2") (pin "1") (pinfunction "1_1") (pintype "passive"))
      (node (ref "U1") (pin "P$A23") (pinfunction "XC2_P$A23") (pintype "output"))
      (node (ref "X1") (pin "3") (pinfunction "3_3") (pintype "passive"))
    )
    (net (code "58") (name "OUT+") (class "Default")
      (node (ref "IC2") (pin "A3") (pinfunction "OUT+_A3") (pintype "bidirectional"))
      (node (ref "TP_OP") (pin "TP") (pinfunction "TP_TP") (pintype "input"))
    )
    (net (code "59") (name "OUT-") (class "Default")
      (node (ref "IC2") (pin "C3") (pinfunction "OUT-_C3") (pintype "bidirectional"))
      (node (ref "TP_ON") (pin "TP") (pinfunction "TP_TP") (pintype "input"))
    )
    (net (code "60") (name "P0.00{slash}XL1") (class "Default")
      (node (ref "C17") (pin "2") (pinfunction "2_2") (pintype "passive"))
      (node (ref "U1") (pin "P$D2") (pinfunction "P0.00/XL1_P$D2") (pintype "bidirectional"))
      (node (ref "X2") (pin "1") (pinfunction "1_1") (pintype "passive"))
    )
    (net (code "61") (name "P0.01{slash}XL2") (class "Default")
      (node (ref "C18") (pin "2") (pinfunction "2_2") (pintype "passive"))
      (node (ref "U1") (pin "P$F2") (pinfunction "P0.01/XL2_P$F2") (pintype "bidirectional"))
      (node (ref "X2") (pin "2") (pinfunction "2_2") (pintype "passive"))
    )
    (net (code "62") (name "P0.04") (class "Default")
      (node (ref "U1") (pin "P$J1") (pinfunction "P0.04/AIN2_P$J1") (pintype "bidirectional"))
    )
    (net (code "63") (name "P0.09") (class "Default")
      (node (ref "U1") (pin "P$L24") (pinfunction "P0.09/NFC1_P$L24") (pintype "bidirectional"))
    )
    (net (code "64") (name "P0.13{slash}1.5D") (class "Default")
      (node (ref "C30") (pin "2") (pinfunction "2_2") (pintype "passive"))
      (node (ref "R5") (pin "1") (pinfunction "1_1") (pintype "bidirectional"))
      (node (ref "SW_UP") (pin "2") (pinfunction "2_2") (pintype "passive"))
    )
    (net (code "65") (name "P0.13{slash}2.6C") (class "Default")
      (node (ref "U1") (pin "P$AD8") (pinfunction "P0.13_P$AD8") (pintype "bidirectional"))
    )
    (net (code "66") (name "P0.14{slash}1.5D") (class "Default")
      (node (ref "C31") (pin "2") (pinfunction "2_2") (pintype "passive"))
      (node (ref "R8") (pin "1") (pinfunction "1_1") (pintype "bidirectional"))
      (node (ref "SW_ENT") (pin "2") (pinfunction "2_2") (pintype "passive"))
    )
    (net (code "67") (name "P0.14{slash}2.7C") (class "Default")
      (node (ref "U1") (pin "P$AC9") (pinfunction "P0.14_P$AC9") (pintype "bidirectional"))
    )
    (net (code "68") (name "P0.19") (class "Default")
      (node (ref "U1") (pin "P$AC15") (pinfunction "P0.19_P$AC15") (pintype "bidirectional"))
    )
    (net (code "69") (name "P0.20") (class "Default")
      (node (ref "U1") (pin "P$AD16") (pinfunction "P0.20_P$AD16") (pintype "bidirectional"))
    )
    (net (code "70") (name "P0.21") (class "Default")
      (node (ref "U1") (pin "P$AC17") (pinfunction "P0.21_P$AC17") (pintype "bidirectional"))
    )
    (net (code "71") (name "P0.22") (class "Default")
      (node (ref "U1") (pin "P$AD18") (pinfunction "P0.22_P$AD18") (pintype "bidirectional"))
    )
    (net (code "72") (name "P0.23") (class "Default")
      (node (ref "U1") (pin "P$AC19") (pinfunction "P0.23_P$AC19") (pintype "bidirectional"))
    )
    (net (code "73") (name "P0.24") (class "Default")
      (node (ref "U1") (pin "P$AD20") (pinfunction "P0.24_P$AD20") (pintype "bidirectional"))
    )
    (net (code "74") (name "P0.25") (class "Default")
      (node (ref "U1") (pin "P$AC21") (pinfunction "P0.25_P$AC21") (pintype "bidirectional"))
    )
    (net (code "75") (name "P0.26") (class "Default")
      (node (ref "U1") (pin "P$G1") (pinfunction "P0.26_P$G1") (pintype "bidirectional"))
    )
    (net (code "76") (name "P0.27") (class "Default")
      (node (ref "U1") (pin "P$H2") (pinfunction "P0.27_P$H2") (pintype "bidirectional"))
    )
    (net (code "77") (name "P0.28") (class "Default")
      (node (ref "U1") (pin "P$B11") (pinfunction "P0.28/AIN4_P$B11") (pintype "bidirectional"))
    )
    (net (code "78") (name "P0.29") (class "Default")
      (node (ref "U1") (pin "P$A10") (pinfunction "P0.29/AIN5_P$A10") (pintype "bidirectional"))
    )
    (net (code "79") (name "P0.30") (class "Default")
      (node (ref "U1") (pin "P$B9") (pinfunction "P0.30/AIN6_P$B9") (pintype "bidirectional"))
    )
    (net (code "80") (name "P0.31") (class "Default")
      (node (ref "U1") (pin "P$A8") (pinfunction "P0.31/AIN7_P$A8") (pintype "bidirectional"))
    )
    (net (code "81") (name "P1.01{slash}1.6C") (class "Default")
      (node (ref "Q1") (pin "1") (pinfunction "G_1") (pintype "bidirectional"))
      (node (ref "R_PWR_EPD") (pin "1") (pinfunction "1_1") (pintype "bidirectional"))
    )
    (net (code "82") (name "P1.01{slash}2.4B") (class "Default")
      (node (ref "U1") (pin "P$Y23") (pinfunction "P1.01_P$Y23") (pintype "bidirectional"))
    )
    (net (code "83") (name "P1.02{slash}1.6C") (class "Default")
      (node (ref "C29") (pin "2") (pinfunction "2_2") (pintype "passive"))
      (node (ref "R7") (pin "1") (pinfunction "1_1") (pintype "bidirectional"))
      (node (ref "SW_DN") (pin "2") (pinfunction "2_2") (pintype "passive"))
    )
    (net (code "84") (name "P1.02{slash}2.8C") (class "Default")
      (node (ref "U1") (pin "P$W24") (pinfunction "P1.02_P$W24") (pintype "bidirectional"))
    )
    (net (code "85") (name "P1.03") (class "Default")
      (node (ref "U1") (pin "P$V23") (pinfunction "P1.03_P$V23") (pintype "bidirectional"))
    )
    (net (code "86") (name "P1.04") (class "Default")
      (node (ref "U1") (pin "P$U24") (pinfunction "P1.04_P$U24") (pintype "bidirectional"))
    )
    (net (code "87") (name "P1.05") (class "Default")
      (node (ref "U1") (pin "P$T23") (pinfunction "P1.05_P$T23") (pintype "bidirectional"))
    )
    (net (code "88") (name "P1.06") (class "Default")
      (node (ref "U1") (pin "P$R24") (pinfunction "P1.06_P$R24") (pintype "bidirectional"))
    )
    (net (code "89") (name "P1.07") (class "Default")
      (node (ref "U1") (pin "P$P23") (pinfunction "P1.07_P$P23") (pintype "bidirectional"))
    )
    (net (code "90") (name "P1.09") (class "Default")
      (node (ref "U1") (pin "P$R1") (pinfunction "P1.09_P$R1") (pintype "bidirectional"))
    )
    (net (code "91") (name "P1.10") (class "Default")
      (node (ref "U1") (pin "P$A20") (pinfunction "P1.10_P$A20") (pintype "bidirectional"))
    )
    (net (code "92") (name "P1.11") (class "Default")
      (node (ref "U1") (pin "P$B19") (pinfunction "P1.11_P$B19") (pintype "bidirectional"))
    )
    (net (code "93") (name "P1.12") (class "Default")
      (node (ref "U1") (pin "P$B17") (pinfunction "P1.12_P$B17") (pintype "bidirectional"))
    )
    (net (code "94") (name "P1.13") (class "Default")
      (node (ref "U1") (pin "P$A16") (pinfunction "P1.13_P$A16") (pintype "bidirectional"))
    )
    (net (code "95") (name "P1.14") (class "Default")
      (node (ref "U1") (pin "P$B15") (pinfunction "P1.14_P$B15") (pintype "bidirectional"))
    )
    (net (code "96") (name "P1.15") (class "Default")
      (node (ref "U1") (pin "P$A14") (pinfunction "P1.15_P$A14") (pintype "bidirectional"))
    )
    (net (code "97") (name "PMIC_INT") (class "Default")
      (node (ref "IC1") (pin "A1") (pinfunction "~{INT}_A1") (pintype "bidirectional"))
      (node (ref "U1") (pin "P$T2") (pinfunction "P0.11_P$T2") (pintype "bidirectional"))
    )
    (net (code "98") (name "PREVGH") (class "Default")
      (node (ref "D5") (pin "1") (pinfunction "K_1") (pintype "bidirectional"))
      (node (ref "EPD_C9") (pin "2") (pinfunction "2_2") (pintype "passive"))
      (node (ref "J1") (pin "21") (pinfunction "21_21") (pintype "bidirectional"))
    )
    (net (code "99") (name "PREVGL") (class "Default")
      (node (ref "D2") (pin "2") (pinfunction "A_2") (pintype "bidirectional"))
      (node (ref "EPD_C11") (pin "2") (pinfunction "2_2") (pintype "passive"))
      (node (ref "J1") (pin "23") (pinfunction "23_23") (pintype "bidirectional"))
    )
    (net (code "100") (name "RESE") (class "Default")
      (node (ref "J1") (pin "3") (pinfunction "3_3") (pintype "bidirectional"))
      (node (ref "Q3") (pin "2") (pinfunction "S_2") (pintype "bidirectional"))
      (node (ref "R1_EP_DR") (pin "2") (pinfunction "2_2") (pintype "bidirectional"))
    )
    (net (code "101") (name "RESET") (class "Default")
      (node (ref "J2") (pin "6") (pinfunction "6_6") (pintype "bidirectional"))
      (node (ref "TP_RESET") (pin "TP") (pinfunction "TP_TP") (pintype "input"))
      (node (ref "U1") (pin "P$AC13") (pinfunction "P0.18/RESET_P$AC13") (pintype "bidirectional"))
    )
    (net (code "102") (name "RF") (class "Default")
      (node (ref "ANT1") (pin "1") (pinfunction "FEED_1") (pintype "input"))
      (node (ref "C22") (pin "1") (pinfunction "1_1") (pintype "passive"))
      (node (ref "C4") (pin "1") (pinfunction "1_1") (pintype "passive"))
      (node (ref "L1") (pin "2") (pinfunction "2_2") (pintype "passive"))
    )
    (net (code "103") (name "SCK{slash}1.5B") (class "Default")
      (node (ref "J1") (pin "13") (pinfunction "13_13") (pintype "bidirectional"))
    )
    (net (code "104") (name "SCK{slash}2.2D") (class "Default")
      (node (ref "U1") (pin "P$A12") (pinfunction "P0.02/AIN0_P$A12") (pintype "bidirectional"))
    )
    (net (code "105") (name "SCL{slash}1.4C") (class "Default")
      (node (ref "IC2") (pin "C1") (pinfunction "SCL_C1") (pintype "bidirectional"))
      (node (ref "U3") (pin "7") (pinfunction "SCL_7") (pintype "input"))
    )
    (net (code "106") (name "SCL{slash}2.4C") (class "Default")
      (node (ref "IC1") (pin "B1") (pinfunction "SCL_B1") (pintype "bidirectional"))
      (node (ref "IC3") (pin "12") (pinfunction "SCX_12") (pintype "bidirectional"))
      (node (ref "R17") (pin "2") (pinfunction "2_2") (pintype "bidirectional"))
      (node (ref "R4") (pin "1") (pinfunction "1_1") (pintype "bidirectional"))
      (node (ref "TP_SCL") (pin "TP") (pinfunction "TP_TP") (pintype "input"))
      (node (ref "U1") (pin "P$M2") (pinfunction "P0.07_P$M2") (pintype "bidirectional"))
    )
    (net (code "107") (name "SDA{slash}1.4C") (class "Default")
      (node (ref "IC2") (pin "B2") (pinfunction "SDA_B2") (pintype "bidirectional"))
      (node (ref "U3") (pin "8") (pinfunction "SDA_8") (pintype "bidirectional"))
    )
    (net (code "108") (name "SDA{slash}2.4C") (class "Default")
      (node (ref "IC1") (pin "C1") (pinfunction "SDA_C1") (pintype "bidirectional"))
      (node (ref "IC3") (pin "2") (pinfunction "SDX_2") (pintype "bidirectional"))
      (node (ref "R18") (pin "2") (pinfunction "2_2") (pintype "bidirectional"))
      (node (ref "R2") (pin "1") (pinfunction "1_1") (pintype "bidirectional"))
      (node (ref "TP_SDA") (pin "TP") (pinfunction "TP_TP") (pintype "input"))
      (node (ref "U1") (pin "P$L1") (pinfunction "P0.06_P$L1") (pintype "bidirectional"))
    )
    (net (code "109") (name "SWDCLK") (class "Default")
      (node (ref "J2") (pin "4") (pinfunction "4_4") (pintype "bidirectional"))
      (node (ref "TP_SWDCLK") (pin "TP") (pinfunction "TP_TP") (pintype "input"))
      (node (ref "U1") (pin "P$AA24") (pinfunction "SWDCLK_P$AA24") (pintype "input"))
    )
    (net (code "110") (name "SWDIO") (class "Default")
      (node (ref "J2") (pin "2") (pinfunction "2_2") (pintype "bidirectional"))
      (node (ref "TP_SWDIO") (pin "TP") (pinfunction "TP_TP") (pintype "input"))
      (node (ref "U1") (pin "P$AC24") (pinfunction "SWDIO_P$AC24") (pintype "bidirectional"))
    )
    (net (code "111") (name "SWO") (class "Default")
      (node (ref "TP_SWO") (pin "TP") (pinfunction "TP_TP") (pintype "input"))
      (node (ref "U1") (pin "P$AD22") (pinfunction "P1.00_P$AD22") (pintype "bidirectional"))
    )
    (net (code "112") (name "VBAT{slash}1.2A") (class "Default")
      (node (ref "C27") (pin "2") (pinfunction "2_2") (pintype "passive"))
      (node (ref "TP_VBAT") (pin "TP") (pinfunction "TP_TP") (pintype "input"))
      (node (ref "U3") (pin "2") (pinfunction "CELL_2") (pintype "power_in"))
      (node (ref "U3") (pin "3") (pinfunction "VDD_3") (pintype "power_in"))
    )
    (net (code "113") (name "VBAT{slash}2.5C") (class "Default")
      (node (ref "C37") (pin "2") (pinfunction "2_2") (pintype "passive"))
      (node (ref "IC1") (pin "C2") (pinfunction "BAT_C2") (pintype "bidirectional"))
    )
    (net (code "114") (name "VBUS{slash}1.5D") (class "Default")
      (node (ref "C42") (pin "1") (pinfunction "1_1") (pintype "passive"))
      (node (ref "C43") (pin "2") (pinfunction "2_2") (pintype "passive"))
      (node (ref "D3") (pin "5") (pinfunction "VBUS_5") (pintype "bidirectional"))
      (node (ref "J4") (pin "A4_B9") (pinfunction "VBUS_A4_B9") (pintype "power_in"))
      (node (ref "J4") (pin "A9_B4") (pinfunction "VBUS_A9_B4") (pintype "power_in"))
    )
    (net (code "115") (name "VBUS{slash}2.6D") (class "Default")
      (node (ref "C21") (pin "1") (pinfunction "1_1") (pintype "passive"))
      (node (ref "C38") (pin "2") (pinfunction "2_2") (pintype "passive"))
      (node (ref "IC1") (pin "A2") (pinfunction "IN_A2") (pintype "bidirectional"))
      (node (ref "U1") (pin "P$AD2") (pinfunction "VBUS_P$AD2") (pintype "power_in"))
    )
    (net (code "116") (name "VREG") (class "Default")
      (node (ref "C23") (pin "2") (pinfunction "2_2") (pintype "passive"))
      (node (ref "C24") (pin "2") (pinfunction "2_2") (pintype "passive"))
      (node (ref "C39") (pin "1") (pinfunction "1_1") (pintype "passive"))
      (node (ref "IC1") (pin "B2") (pinfunction "SYS_B2") (pintype "bidirectional"))
      (node (ref "IC9") (pin "A1") (pinfunction "EN_A1") (pintype "bidirectional"))
      (node (ref "IC9") (pin "A2") (pinfunction "VIN_1_A2") (pintype "bidirectional"))
      (node (ref "IC9") (pin "A3") (pinfunction "VIN_2_A3") (pintype "bidirectional"))
      (node (ref "TP_VREG") (pin "TP") (pinfunction "TP_TP") (pintype "input"))
    )
    (net (code "117") (name "unconnected-(ANT1-NC-Pad2)") (class "Default")
      (node (ref "ANT1") (pin "2") (pinfunction "NC_2") (pintype "no_connect"))
    )
    (net (code "118") (name "unconnected-(IC3-ASCL-Pad11)") (class "Default")
      (node (ref "IC3") (pin "11") (pinfunction "ASCL_11") (pintype "bidirectional"))
    )
    (net (code "119") (name "unconnected-(IC3-ASDA-Pad4)") (class "Default")
      (node (ref "IC3") (pin "4") (pinfunction "ASDA_4") (pintype "bidirectional"))
    )
    (net (code "120") (name "unconnected-(J1-Pad1)") (class "Default")
      (node (ref "J1") (pin "1") (pinfunction "1_1") (pintype "bidirectional"))
    )
    (net (code "121") (name "unconnected-(J1-Pad6)") (class "Default")
      (node (ref "J1") (pin "6") (pinfunction "6_6") (pintype "bidirectional"))
    )
    (net (code "122") (name "unconnected-(J1-Pad7)") (class "Default")
      (node (ref "J1") (pin "7") (pinfunction "7_7") (pintype "bidirectional"))
    )
    (net (code "123") (name "unconnected-(J4-SBU1-PadA8)") (class "Default")
      (node (ref "J4") (pin "A8") (pinfunction "SBU1_A8") (pintype "bidirectional"))
    )
    (net (code "124") (name "unconnected-(J4-SBU2-PadB8)") (class "Default")
      (node (ref "J4") (pin "B8") (pinfunction "SBU2_B8") (pintype "bidirectional"))
    )
    (net (code "125") (name "unconnected-(U1-DCCH-PadP$AB2)") (class "Default")
      (node (ref "U1") (pin "P$AB2") (pinfunction "DCCH_P$AB2") (pintype "bidirectional"))
    )
  )
)
